# Dual_555_Police_Strobe.net
KiCad netlist of a schematic drawn in EAGLE
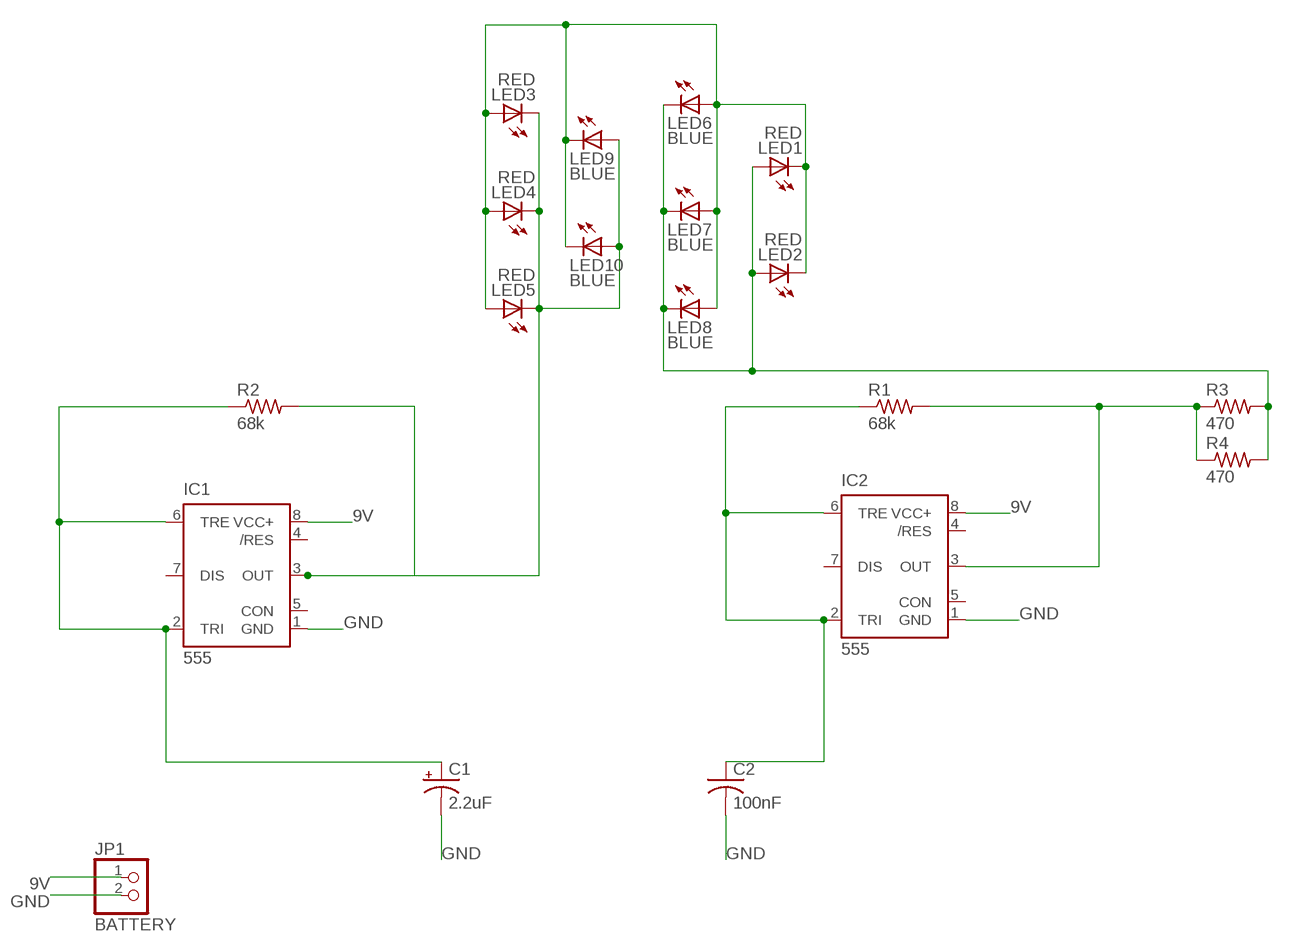
[diagram p0: schematic, sheet 1]

(export (version "E")
  (design (tool "Eeschema 10.0.6"))
  (components
    (comp (ref "C1")
      (value "2.2uF")
      (footprint "eagle-import:E2,5-6")
      (libsource (lib "eagle-import") (part "CPOL-USE2.5-6"))
    )
    (comp (ref "C2")
      (value "100nF")
      (footprint "eagle-import:C025-050X050")
      (libsource (lib "eagle-import") (part "C-US025-050X050"))
    )
    (comp (ref "IC1")
      (value "555")
      (footprint "eagle-import:DIP08")
      (libsource (lib "eagle-import") (part "555P"))
    )
    (comp (ref "IC2")
      (value "555")
      (footprint "eagle-import:DIP08")
      (libsource (lib "eagle-import") (part "555P"))
    )
    (comp (ref "JP1")
      (value "BATTERY")
      (footprint "eagle-import:1X02")
      (libsource (lib "eagle-import") (part "PINHD-1X2"))
    )
    (comp (ref "LED1")
      (value "RED")
      (footprint "eagle-import:LED5MM")
      (libsource (lib "eagle-import") (part "LED5MM"))
    )
    (comp (ref "LED2")
      (value "RED")
      (footprint "eagle-import:LED5MM")
      (libsource (lib "eagle-import") (part "LED5MM"))
    )
    (comp (ref "LED3")
      (value "RED")
      (footprint "eagle-import:LED5MM")
      (libsource (lib "eagle-import") (part "LED5MM"))
    )
    (comp (ref "LED4")
      (value "RED")
      (footprint "eagle-import:LED5MM")
      (libsource (lib "eagle-import") (part "LED5MM"))
    )
    (comp (ref "LED5")
      (value "RED")
      (footprint "eagle-import:LED5MM")
      (libsource (lib "eagle-import") (part "LED5MM"))
    )
    (comp (ref "LED6")
      (value "BLUE")
      (footprint "eagle-import:LED5MM")
      (libsource (lib "eagle-import") (part "LED5MM"))
    )
    (comp (ref "LED7")
      (value "BLUE")
      (footprint "eagle-import:LED5MM")
      (libsource (lib "eagle-import") (part "LED5MM"))
    )
    (comp (ref "LED8")
      (value "BLUE")
      (footprint "eagle-import:LED5MM")
      (libsource (lib "eagle-import") (part "LED5MM"))
    )
    (comp (ref "LED9")
      (value "BLUE")
      (footprint "eagle-import:LED5MM")
      (libsource (lib "eagle-import") (part "LED5MM"))
    )
    (comp (ref "LED10")
      (value "BLUE")
      (footprint "eagle-import:LED5MM")
      (libsource (lib "eagle-import") (part "LED5MM"))
    )
    (comp (ref "R1")
      (value "68k")
      (footprint "eagle-import:0207_10")
      (libsource (lib "eagle-import") (part "R-US_0207/10"))
    )
    (comp (ref "R2")
      (value "68k")
      (footprint "eagle-import:0207_10")
      (libsource (lib "eagle-import") (part "R-US_0207/10"))
    )
    (comp (ref "R3")
      (value "470")
      (footprint "eagle-import:0207_10")
      (libsource (lib "eagle-import") (part "R-US_0207/10"))
    )
    (comp (ref "R4")
      (value "470")
      (footprint "eagle-import:0207_10")
      (libsource (lib "eagle-import") (part "R-US_0207/10"))
    )
  )
  (nets
    (net (code "1") (name "9V") (class "Default")
      (node (ref "IC1") (pin "8") (pinfunction "VCC+_8") (pintype "power_in"))
      (node (ref "IC2") (pin "8") (pinfunction "VCC+_8") (pintype "power_in"))
      (node (ref "JP1") (pin "1") (pinfunction "1_1") (pintype "passive"))
    )
    (net (code "2") (name "GND") (class "Default")
      (node (ref "C1") (pin "-") (pinfunction "-_-") (pintype "passive"))
      (node (ref "C2") (pin "2") (pinfunction "2_2") (pintype "passive"))
      (node (ref "IC1") (pin "1") (pinfunction "GND_1") (pintype "power_in"))
      (node (ref "IC2") (pin "1") (pinfunction "GND_1") (pintype "power_in"))
      (node (ref "JP1") (pin "2") (pinfunction "2_2") (pintype "passive"))
    )
    (net (code "3") (name "Net-(IC1-OUT)") (class "Default")
      (node (ref "IC1") (pin "3") (pinfunction "OUT_3") (pintype "output"))
      (node (ref "LED10") (pin "A") (pinfunction "A_A") (pintype "passive"))
      (node (ref "LED3") (pin "K") (pinfunction "C_K") (pintype "passive"))
      (node (ref "LED4") (pin "K") (pinfunction "C_K") (pintype "passive"))
      (node (ref "LED5") (pin "K") (pinfunction "C_K") (pintype "passive"))
      (node (ref "LED9") (pin "A") (pinfunction "A_A") (pintype "passive"))
      (node (ref "R2") (pin "2") (pinfunction "2_2") (pintype "passive"))
    )
    (net (code "4") (name "Net-(IC1-TRE)") (class "Default")
      (node (ref "C1") (pin "+") (pinfunction "+_+") (pintype "passive"))
      (node (ref "IC1") (pin "2") (pinfunction "TRI_2") (pintype "input"))
      (node (ref "IC1") (pin "6") (pinfunction "TRE_6") (pintype "input"))
      (node (ref "R2") (pin "1") (pinfunction "1_1") (pintype "passive"))
    )
    (net (code "5") (name "Net-(IC2-OUT)") (class "Default")
      (node (ref "IC2") (pin "3") (pinfunction "OUT_3") (pintype "output"))
      (node (ref "R1") (pin "2") (pinfunction "2_2") (pintype "passive"))
      (node (ref "R3") (pin "1") (pinfunction "1_1") (pintype "passive"))
      (node (ref "R4") (pin "1") (pinfunction "1_1") (pintype "passive"))
    )
    (net (code "6") (name "Net-(IC2-TRE)") (class "Default")
      (node (ref "C2") (pin "1") (pinfunction "1_1") (pintype "passive"))
      (node (ref "IC2") (pin "2") (pinfunction "TRI_2") (pintype "input"))
      (node (ref "IC2") (pin "6") (pinfunction "TRE_6") (pintype "input"))
      (node (ref "R1") (pin "1") (pinfunction "1_1") (pintype "passive"))
    )
    (net (code "7") (name "Net-(LED1-C)") (class "Default")
      (node (ref "LED1") (pin "K") (pinfunction "C_K") (pintype "passive"))
      (node (ref "LED10") (pin "K") (pinfunction "C_K") (pintype "passive"))
      (node (ref "LED2") (pin "K") (pinfunction "C_K") (pintype "passive"))
      (node (ref "LED3") (pin "A") (pinfunction "A_A") (pintype "passive"))
      (node (ref "LED4") (pin "A") (pinfunction "A_A") (pintype "passive"))
      (node (ref "LED5") (pin "A") (pinfunction "A_A") (pintype "passive"))
      (node (ref "LED6") (pin "A") (pinfunction "A_A") (pintype "passive"))
      (node (ref "LED7") (pin "A") (pinfunction "A_A") (pintype "passive"))
      (node (ref "LED8") (pin "A") (pinfunction "A_A") (pintype "passive"))
      (node (ref "LED9") (pin "K") (pinfunction "C_K") (pintype "passive"))
    )
    (net (code "8") (name "Net-(LED6-C)") (class "Default")
      (node (ref "LED1") (pin "A") (pinfunction "A_A") (pintype "passive"))
      (node (ref "LED2") (pin "A") (pinfunction "A_A") (pintype "passive"))
      (node (ref "LED6") (pin "K") (pinfunction "C_K") (pintype "passive"))
      (node (ref "LED7") (pin "K") (pinfunction "C_K") (pintype "passive"))
      (node (ref "LED8") (pin "K") (pinfunction "C_K") (pintype "passive"))
      (node (ref "R3") (pin "2") (pinfunction "2_2") (pintype "passive"))
      (node (ref "R4") (pin "2") (pinfunction "2_2") (pintype "passive"))
    )
    (net (code "9") (name "unconnected-(IC1-CON-Pad5)") (class "Default")
      (node (ref "IC1") (pin "5") (pinfunction "CON_5") (pintype "input"))
    )
    (net (code "10") (name "unconnected-(IC1-DIS-Pad7)") (class "Default")
      (node (ref "IC1") (pin "7") (pinfunction "DIS_7") (pintype "input"))
    )
    (net (code "11") (name "unconnected-(IC1-{slash}RES-Pad4)") (class "Default")
      (node (ref "IC1") (pin "4") (pinfunction "/RES_4") (pintype "input"))
    )
    (net (code "12") (name "unconnected-(IC2-CON-Pad5)") (class "Default")
      (node (ref "IC2") (pin "5") (pinfunction "CON_5") (pintype "input"))
    )
    (net (code "13") (name "unconnected-(IC2-DIS-Pad7)") (class "Default")
      (node (ref "IC2") (pin "7") (pinfunction "DIS_7") (pintype "input"))
    )
    (net (code "14") (name "unconnected-(IC2-{slash}RES-Pad4)") (class "Default")
      (node (ref "IC2") (pin "4") (pinfunction "/RES_4") (pintype "input"))
    )
  )
)
